# SCH_Rohans-Card_2024-07-01.net
KiCad netlist of a schematic drawn in EasyEDA
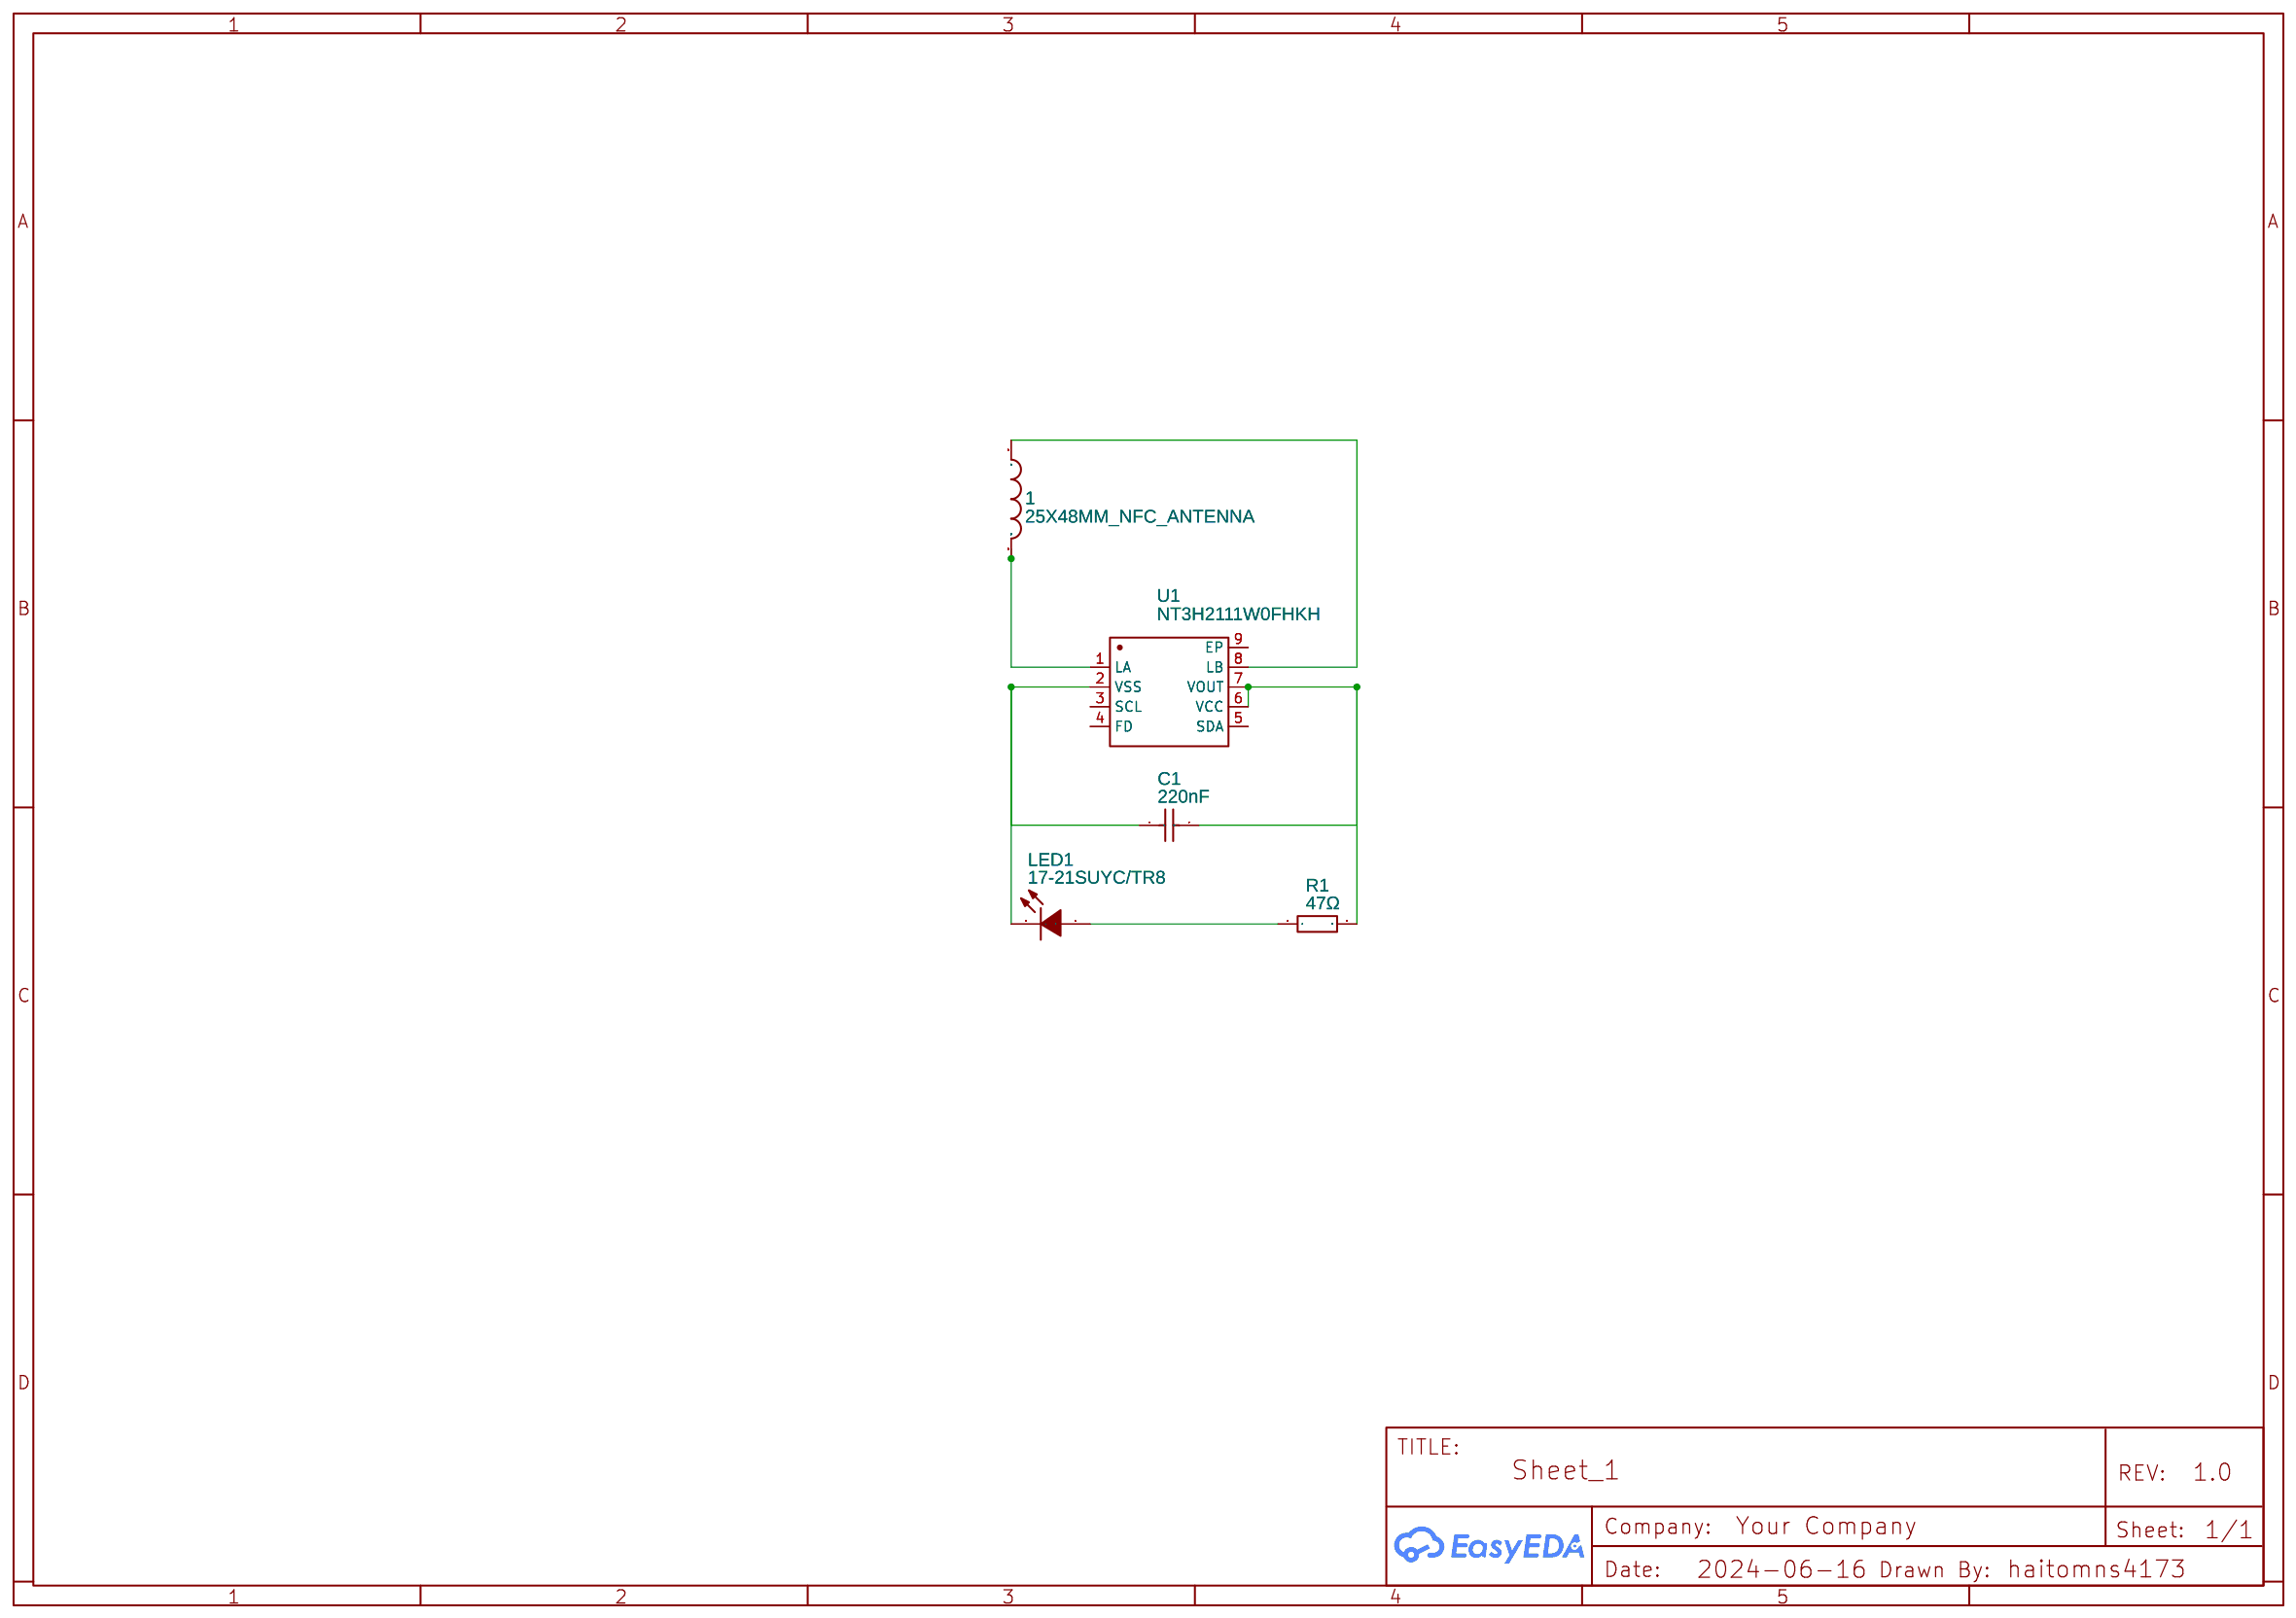
[diagram p0: schematic sheet]

(export (version "E")
  (design (tool "Eeschema 10.0.6"))
  (components
    (comp (ref "1") (value "25X48MM_NFC_ANTENNA") (libsource (lib "") (part "25X48MM_NFC_ANTENNA")))
    (comp (ref "C1")
      (value "220nF")
      (fields
        (field (name "Manufacturer Part") "CL10B224KA8NNNC")
        (field (name "Manufacturer") "SAMSUNG(三星)")
      )
      (libsource (lib "") (part "CL10B224KA8NNNC"))
    )
    (comp (ref "LED1")
      (value "17-21SUYC/TR8")
      (fields (field (name "Manufacturer Part") "KT-0805黄灯") (field (name "Manufacturer") "KENTO"))
      (libsource (lib "") (part "17-21SUYC/TR8"))
    )
    (comp (ref "R1")
      (value "47Ω")
      (fields
        (field (name "Manufacturer Part") "0603WAF470JT5E")
        (field (name "Manufacturer") "UNI-ROYAL(厚声)")
      )
      (libsource (lib "") (part "0603WAF470JT5E"))
    )
    (comp (ref "U1")
      (value "NT3H2111W0FHKH")
      (fields (field (name "Manufacturer") "NXP(恩智浦)"))
      (libsource (lib "") (part "NT3H2111W0FHKH"))
    )
  )
  (nets
    (net (code "1") (name "Net-(LED1-+)") (class "Default")
      (node (ref "LED1") (pin "1") (pinfunction "+_1") (pintype "unspecified"))
      (node (ref "R1") (pin "1") (pinfunction "1_1") (pintype "input"))
    )
    (net (code "2") (name "Net-(LED1--)") (class "Default")
      (node (ref "C1") (pin "1") (pinfunction "1_1") (pintype "input"))
      (node (ref "LED1") (pin "2") (pinfunction "-_2") (pintype "unspecified"))
      (node (ref "U1") (pin "2") (pinfunction "VSS_2") (pintype "unspecified"))
    )
    (net (code "3") (name "Net-(U1-LA)") (class "Default")
      (node (ref "1") (pin "P$2") (pinfunction "P$2_P$2") (pintype "bidirectional"))
      (node (ref "U1") (pin "1") (pinfunction "LA_1") (pintype "unspecified"))
    )
    (net (code "4") (name "Net-(U1-LB)") (class "Default")
      (node (ref "1") (pin "P$1") (pinfunction "P$1_P$1") (pintype "bidirectional"))
      (node (ref "U1") (pin "8") (pinfunction "LB_8") (pintype "unspecified"))
    )
    (net (code "5") (name "Net-(U1-VCC)") (class "Default")
      (node (ref "C1") (pin "2") (pinfunction "2_2") (pintype "input"))
      (node (ref "R1") (pin "2") (pinfunction "2_2") (pintype "input"))
      (node (ref "U1") (pin "6") (pinfunction "VCC_6") (pintype "unspecified"))
      (node (ref "U1") (pin "7") (pinfunction "VOUT_7") (pintype "unspecified"))
    )
    (net (code "6") (name "unconnected-(U1-EP-Pad9)") (class "Default")
      (node (ref "U1") (pin "9") (pinfunction "EP_9") (pintype "unspecified"))
    )
    (net (code "7") (name "unconnected-(U1-FD-Pad4)") (class "Default")
      (node (ref "U1") (pin "4") (pinfunction "FD_4") (pintype "unspecified"))
    )
    (net (code "8") (name "unconnected-(U1-SCL-Pad3)") (class "Default")
      (node (ref "U1") (pin "3") (pinfunction "SCL_3") (pintype "unspecified"))
    )
    (net (code "9") (name "unconnected-(U1-SDA-Pad5)") (class "Default")
      (node (ref "U1") (pin "5") (pinfunction "SDA_5") (pintype "unspecified"))
    )
  )
)
